# Sheet1.net
KiCad netlist of a schematic drawn in Altium Designer
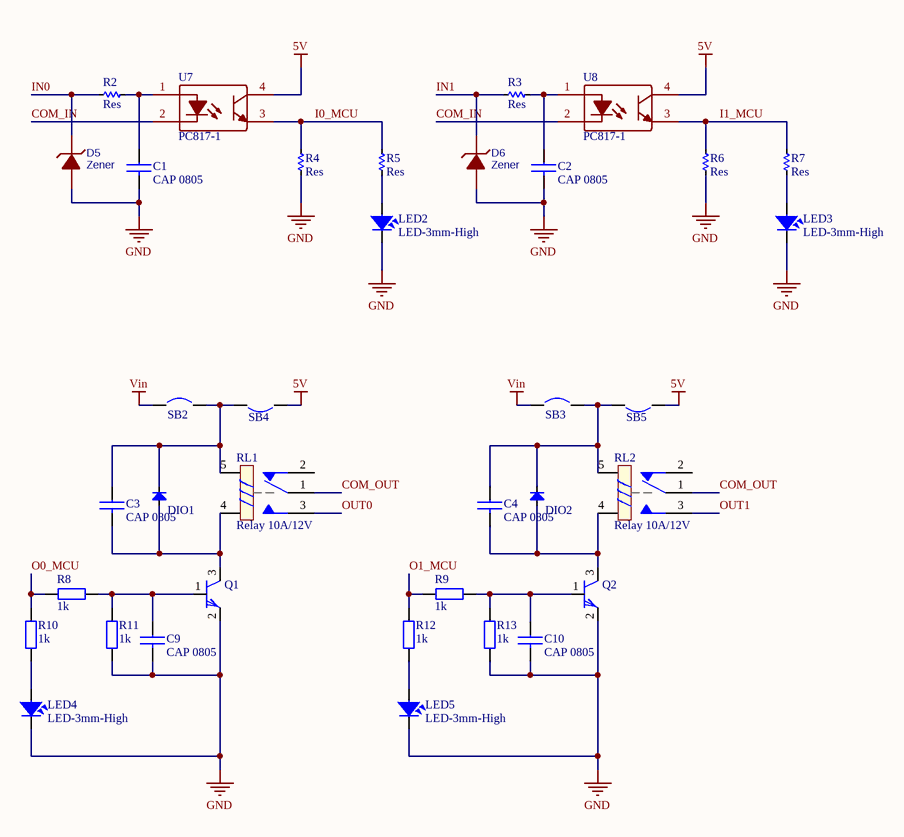
[diagram p0: Sheet1.SchDoc]

(export (version "E")
  (design (tool "Eeschema 10.0.6"))
  (components
    (comp (ref "C1") (value "CAP 0805") (footprint "0805") (libsource (lib "Cty1") (part "CAP 0805")))
    (comp (ref "C2") (value "CAP 0805") (footprint "0805") (libsource (lib "Cty1") (part "CAP 0805")))
    (comp (ref "C3") (value "CAP 0805") (footprint "0805") (libsource (lib "Cty1") (part "CAP 0805")))
    (comp (ref "C4") (value "CAP 0805") (footprint "0805") (libsource (lib "Cty1") (part "CAP 0805")))
    (comp (ref "C9") (value "CAP 0805") (footprint "0805") (libsource (lib "Cty1") (part "CAP 0805")))
    (comp (ref "C10") (value "CAP 0805") (footprint "0805") (libsource (lib "Cty1") (part "CAP 0805")))
    (comp (ref "D5")
      (value "Zener")
      (footprint "SOD80C")
      (fields
        (field (name "BOM_SUPPLIER PART") "C108433")
        (field (name "BOM_MANUFACTURER PART") "BZV55-C15")
        (field (name "CONTRIBUTOR") "LCSC")
      )
      (libsource (lib "Zener-Diode") (part "Zener"))
    )
    (comp (ref "D6")
      (value "Zener")
      (footprint "SOD80C")
      (fields
        (field (name "BOM_SUPPLIER PART") "C108433")
        (field (name "BOM_MANUFACTURER PART") "BZV55-C15")
        (field (name "CONTRIBUTOR") "LCSC")
      )
      (libsource (lib "Zener-Diode") (part "Zener"))
    )
    (comp (ref "DIO1")
      (value "Diode SMD")
      (footprint "DIO-SMD-106")
      (description "Default Diode")
      (fields (field (name "PUBLISHER") "Altium Limited"))
      (libsource (lib "Thư Viện Altium FULL HD") (part "Diode SMD"))
    )
    (comp (ref "DIO2")
      (value "Diode SMD")
      (footprint "DIO-SMD-106")
      (description "Default Diode")
      (fields (field (name "PUBLISHER") "Altium Limited"))
      (libsource (lib "Thư Viện Altium FULL HD") (part "Diode SMD"))
    )
    (comp (ref "LED2")
      (value "LED-3mm-High")
      (footprint "LED-3mm-High-Blue")
      (libsource (lib "LED-3mm-High") (part "LED-3mm-High"))
    )
    (comp (ref "LED3")
      (value "LED-3mm-High")
      (footprint "LED-3mm-High-Blue")
      (libsource (lib "LED-3mm-High") (part "LED-3mm-High"))
    )
    (comp (ref "LED4")
      (value "LED-3mm-High")
      (footprint "LED-3mm-High-Blue")
      (libsource (lib "LED-3mm-High") (part "LED-3mm-High"))
    )
    (comp (ref "LED5")
      (value "LED-3mm-High")
      (footprint "LED-3mm-High-Blue")
      (libsource (lib "LED-3mm-High") (part "LED-3mm-High"))
    )
    (comp (ref "Q1")
      (value "C1815")
      (footprint "SOT23 [C1815]")
      (description "Q2SC1815")
      (fields (field (name "PUBLISHER") "Hoang Nguyen"))
      (libsource (lib "hphonglib") (part "C1815"))
    )
    (comp (ref "Q2")
      (value "C1815")
      (footprint "SOT23 [C1815]")
      (description "Q2SC1815")
      (fields (field (name "PUBLISHER") "Hoang Nguyen"))
      (libsource (lib "hphonglib") (part "C1815"))
    )
    (comp (ref "R2")
      (value "Res")
      (footprint "RES-SMD-0805")
      (description "Resistor")
      (fields
        (field (name "MANUFACTURER") "Generic Components")
        (field (name "PUBLISHER") "Altium Hobart Technology Centre")
      )
      (libsource (lib "Thư Viện Altium FULL HD") (part "Res-SMD"))
    )
    (comp (ref "R3")
      (value "Res")
      (footprint "RES-SMD-0805")
      (description "Resistor")
      (fields
        (field (name "MANUFACTURER") "Generic Components")
        (field (name "PUBLISHER") "Altium Hobart Technology Centre")
      )
      (libsource (lib "Thư Viện Altium FULL HD") (part "Res-SMD"))
    )
    (comp (ref "R4")
      (value "Res")
      (footprint "RES-SMD-0805")
      (description "Resistor")
      (fields
        (field (name "MANUFACTURER") "Generic Components")
        (field (name "PUBLISHER") "Altium Hobart Technology Centre")
      )
      (libsource (lib "Thư Viện Altium FULL HD") (part "Res-SMD"))
    )
    (comp (ref "R5")
      (value "Res")
      (footprint "RES-SMD-0805")
      (description "Resistor")
      (fields
        (field (name "MANUFACTURER") "Generic Components")
        (field (name "PUBLISHER") "Altium Hobart Technology Centre")
      )
      (libsource (lib "Thư Viện Altium FULL HD") (part "Res-SMD"))
    )
    (comp (ref "R6")
      (value "Res")
      (footprint "RES-SMD-0805")
      (description "Resistor")
      (fields
        (field (name "MANUFACTURER") "Generic Components")
        (field (name "PUBLISHER") "Altium Hobart Technology Centre")
      )
      (libsource (lib "Thư Viện Altium FULL HD") (part "Res-SMD"))
    )
    (comp (ref "R7")
      (value "Res")
      (footprint "RES-SMD-0805")
      (description "Resistor")
      (fields
        (field (name "MANUFACTURER") "Generic Components")
        (field (name "PUBLISHER") "Altium Hobart Technology Centre")
      )
      (libsource (lib "Thư Viện Altium FULL HD") (part "Res-SMD"))
    )
    (comp (ref "R8")
      (value "1k")
      (footprint "SM-RES-0805")
      (description "Resistor 1/4W")
      (libsource (lib "syhaunguyen") (part "R1/4W"))
    )
    (comp (ref "R9")
      (value "1k")
      (footprint "SM-RES-0805")
      (description "Resistor 1/4W")
      (libsource (lib "syhaunguyen") (part "R1/4W"))
    )
    (comp (ref "R10")
      (value "1k")
      (footprint "SM-RES-0805")
      (description "Resistor 1/4W")
      (libsource (lib "syhaunguyen") (part "R1/4W"))
    )
    (comp (ref "R11")
      (value "1k")
      (footprint "SM-RES-0805")
      (description "Resistor 1/4W")
      (libsource (lib "syhaunguyen") (part "R1/4W"))
    )
    (comp (ref "R12")
      (value "1k")
      (footprint "SM-RES-0805")
      (description "Resistor 1/4W")
      (libsource (lib "syhaunguyen") (part "R1/4W"))
    )
    (comp (ref "R13")
      (value "1k")
      (footprint "SM-RES-0805")
      (description "Resistor 1/4W")
      (libsource (lib "syhaunguyen") (part "R1/4W"))
    )
    (comp (ref "RL1")
      (value "Relay 10A/12V")
      (footprint "RELAY 5")
      (description "Relay SPDT,10A - 12VDC 5 Pin")
      (libsource (lib "Thư Viện Altium FULL HD") (part "Relay 5"))
    )
    (comp (ref "RL2")
      (value "Relay 10A/12V")
      (footprint "RELAY 5")
      (description "Relay SPDT,10A - 12VDC 5 Pin")
      (libsource (lib "Thư Viện Altium FULL HD") (part "Relay 5"))
    )
    (comp (ref "SB2")
      (value "Circuit-Shorter")
      (footprint "Circuit-Shorter")
      (fields (field (name "PUBLISHER") "Altium Limited"))
      (libsource (lib "Circuit-Shorter") (part "Circuit-Shorter"))
    )
    (comp (ref "SB3")
      (value "Circuit-Shorter")
      (footprint "Circuit-Shorter")
      (fields (field (name "PUBLISHER") "Altium Limited"))
      (libsource (lib "Circuit-Shorter") (part "Circuit-Shorter"))
    )
    (comp (ref "SB4")
      (value "Circuit-Shorter")
      (footprint "Circuit-Shorter")
      (fields (field (name "PUBLISHER") "Altium Limited"))
      (libsource (lib "Circuit-Shorter") (part "Circuit-Shorter"))
    )
    (comp (ref "SB5")
      (value "Circuit-Shorter")
      (footprint "Circuit-Shorter")
      (fields (field (name "PUBLISHER") "Altium Limited"))
      (libsource (lib "Circuit-Shorter") (part "Circuit-Shorter"))
    )
    (comp (ref "U7") (value "PC817-1") (footprint "PC817-1-SMD") (libsource (lib "PC817") (part "PC817-1")))
    (comp (ref "U8") (value "PC817-1") (footprint "PC817-1-SMD") (libsource (lib "PC817") (part "PC817-1")))
  )
  (nets
    (net (code "1") (name "/COM_IN") (class "Default")
      (node (ref "U7") (pin "2") (pinfunction "CA_2") (pintype "passive"))
      (node (ref "U8") (pin "2") (pinfunction "CA_2") (pintype "passive"))
    )
    (net (code "2") (name "/COM_OUT") (class "Default")
      (node (ref "RL1") (pin "1") (pinfunction "1_1") (pintype "passive"))
      (node (ref "RL2") (pin "1") (pinfunction "1_1") (pintype "passive"))
    )
    (net (code "3") (name "/I0_MCU") (class "Default")
      (node (ref "R4") (pin "2") (pinfunction "2_2") (pintype "passive"))
      (node (ref "R5") (pin "1") (pinfunction "1_1") (pintype "passive"))
      (node (ref "U7") (pin "3") (pinfunction "EM_3") (pintype "passive"))
    )
    (net (code "4") (name "/I1_MCU") (class "Default")
      (node (ref "R6") (pin "2") (pinfunction "2_2") (pintype "passive"))
      (node (ref "R7") (pin "1") (pinfunction "1_1") (pintype "passive"))
      (node (ref "U8") (pin "3") (pinfunction "EM_3") (pintype "passive"))
    )
    (net (code "5") (name "/IN0") (class "Default")
      (node (ref "D5") (pin "2") (pinfunction "K_2") (pintype "passive"))
      (node (ref "R2") (pin "2") (pinfunction "2_2") (pintype "passive"))
    )
    (net (code "6") (name "/IN1") (class "Default")
      (node (ref "D6") (pin "2") (pinfunction "K_2") (pintype "passive"))
      (node (ref "R3") (pin "2") (pinfunction "2_2") (pintype "passive"))
    )
    (net (code "7") (name "/O0_MCU") (class "Default")
      (node (ref "R10") (pin "2") (pinfunction "2_2") (pintype "passive"))
      (node (ref "R8") (pin "2") (pinfunction "2_2") (pintype "passive"))
    )
    (net (code "8") (name "/O1_MCU") (class "Default")
      (node (ref "R12") (pin "2") (pinfunction "2_2") (pintype "passive"))
      (node (ref "R9") (pin "2") (pinfunction "2_2") (pintype "passive"))
    )
    (net (code "9") (name "/OUT0") (class "Default")
      (node (ref "RL1") (pin "3") (pinfunction "3_3") (pintype "passive"))
    )
    (net (code "10") (name "/OUT1") (class "Default")
      (node (ref "RL2") (pin "3") (pinfunction "3_3") (pintype "passive"))
    )
    (net (code "11") (name "5V") (class "Default")
      (node (ref "SB4") (pin "1") (pinfunction "1_1") (pintype "passive"))
      (node (ref "SB5") (pin "1") (pinfunction "1_1") (pintype "passive"))
      (node (ref "U7") (pin "4") (pinfunction "COL_4") (pintype "passive"))
      (node (ref "U8") (pin "4") (pinfunction "COL_4") (pintype "passive"))
    )
    (net (code "12") (name "GND") (class "Default")
      (node (ref "C1") (pin "2") (pinfunction "2_2") (pintype "passive"))
      (node (ref "C10") (pin "2") (pinfunction "2_2") (pintype "passive"))
      (node (ref "C2") (pin "2") (pinfunction "2_2") (pintype "passive"))
      (node (ref "C9") (pin "2") (pinfunction "2_2") (pintype "passive"))
      (node (ref "D5") (pin "1") (pinfunction "A_1") (pintype "passive"))
      (node (ref "D6") (pin "1") (pinfunction "A_1") (pintype "passive"))
      (node (ref "LED2") (pin "2") (pinfunction "K_2") (pintype "passive"))
      (node (ref "LED3") (pin "2") (pinfunction "K_2") (pintype "passive"))
      (node (ref "LED4") (pin "2") (pinfunction "K_2") (pintype "passive"))
      (node (ref "LED5") (pin "2") (pinfunction "K_2") (pintype "passive"))
      (node (ref "Q1") (pin "2") (pinfunction "E_2") (pintype "passive"))
      (node (ref "Q2") (pin "2") (pinfunction "E_2") (pintype "passive"))
      (node (ref "R11") (pin "2") (pinfunction "2_2") (pintype "passive"))
      (node (ref "R13") (pin "2") (pinfunction "2_2") (pintype "passive"))
      (node (ref "R4") (pin "1") (pinfunction "1_1") (pintype "passive"))
      (node (ref "R6") (pin "1") (pinfunction "1_1") (pintype "passive"))
    )
    (net (code "13") (name "Net-(DIO1-A)") (class "Default")
      (node (ref "C3") (pin "2") (pinfunction "2_2") (pintype "passive"))
      (node (ref "DIO1") (pin "1") (pinfunction "A_1") (pintype "passive"))
      (node (ref "Q1") (pin "3") (pinfunction "C_3") (pintype "passive"))
      (node (ref "RL1") (pin "4") (pinfunction "4_4") (pintype "passive"))
    )
    (net (code "14") (name "Net-(DIO1-K)") (class "Default")
      (node (ref "C3") (pin "1") (pinfunction "1_1") (pintype "passive"))
      (node (ref "DIO1") (pin "2") (pinfunction "K_2") (pintype "passive"))
      (node (ref "RL1") (pin "5") (pinfunction "5_5") (pintype "passive"))
      (node (ref "SB2") (pin "2") (pinfunction "2_2") (pintype "passive"))
      (node (ref "SB4") (pin "2") (pinfunction "2_2") (pintype "passive"))
    )
    (net (code "15") (name "Net-(DIO2-A)") (class "Default")
      (node (ref "C4") (pin "2") (pinfunction "2_2") (pintype "passive"))
      (node (ref "DIO2") (pin "1") (pinfunction "A_1") (pintype "passive"))
      (node (ref "Q2") (pin "3") (pinfunction "C_3") (pintype "passive"))
      (node (ref "RL2") (pin "4") (pinfunction "4_4") (pintype "passive"))
    )
    (net (code "16") (name "Net-(DIO2-K)") (class "Default")
      (node (ref "C4") (pin "1") (pinfunction "1_1") (pintype "passive"))
      (node (ref "DIO2") (pin "2") (pinfunction "K_2") (pintype "passive"))
      (node (ref "RL2") (pin "5") (pinfunction "5_5") (pintype "passive"))
      (node (ref "SB3") (pin "2") (pinfunction "2_2") (pintype "passive"))
      (node (ref "SB5") (pin "2") (pinfunction "2_2") (pintype "passive"))
    )
    (net (code "17") (name "Net-(LED2-A)") (class "Default")
      (node (ref "LED2") (pin "1") (pinfunction "A_1") (pintype "passive"))
      (node (ref "R5") (pin "2") (pinfunction "2_2") (pintype "passive"))
    )
    (net (code "18") (name "Net-(LED3-A)") (class "Default")
      (node (ref "LED3") (pin "1") (pinfunction "A_1") (pintype "passive"))
      (node (ref "R7") (pin "2") (pinfunction "2_2") (pintype "passive"))
    )
    (net (code "19") (name "Net-(LED4-A)") (class "Default")
      (node (ref "LED4") (pin "1") (pinfunction "A_1") (pintype "passive"))
      (node (ref "R10") (pin "1") (pinfunction "1_1") (pintype "passive"))
    )
    (net (code "20") (name "Net-(LED5-A)") (class "Default")
      (node (ref "LED5") (pin "1") (pinfunction "A_1") (pintype "passive"))
      (node (ref "R12") (pin "1") (pinfunction "1_1") (pintype "passive"))
    )
    (net (code "21") (name "Net-(Q1-B)") (class "Default")
      (node (ref "C9") (pin "1") (pinfunction "1_1") (pintype "passive"))
      (node (ref "Q1") (pin "1") (pinfunction "B_1") (pintype "passive"))
      (node (ref "R11") (pin "1") (pinfunction "1_1") (pintype "passive"))
      (node (ref "R8") (pin "1") (pinfunction "1_1") (pintype "passive"))
    )
    (net (code "22") (name "Net-(Q2-B)") (class "Default")
      (node (ref "C10") (pin "1") (pinfunction "1_1") (pintype "passive"))
      (node (ref "Q2") (pin "1") (pinfunction "B_1") (pintype "passive"))
      (node (ref "R13") (pin "1") (pinfunction "1_1") (pintype "passive"))
      (node (ref "R9") (pin "1") (pinfunction "1_1") (pintype "passive"))
    )
    (net (code "23") (name "Net-(U7-AN)") (class "Default")
      (node (ref "C1") (pin "1") (pinfunction "1_1") (pintype "passive"))
      (node (ref "R2") (pin "1") (pinfunction "1_1") (pintype "passive"))
      (node (ref "U7") (pin "1") (pinfunction "AN_1") (pintype "passive"))
    )
    (net (code "24") (name "Net-(U8-AN)") (class "Default")
      (node (ref "C2") (pin "1") (pinfunction "1_1") (pintype "passive"))
      (node (ref "R3") (pin "1") (pinfunction "1_1") (pintype "passive"))
      (node (ref "U8") (pin "1") (pinfunction "AN_1") (pintype "passive"))
    )
    (net (code "25") (name "Vin") (class "Default")
      (node (ref "SB2") (pin "1") (pinfunction "1_1") (pintype "passive"))
      (node (ref "SB3") (pin "1") (pinfunction "1_1") (pintype "passive"))
    )
    (net (code "26") (name "unconnected-(RL1-Pad2)") (class "Default")
      (node (ref "RL1") (pin "2") (pinfunction "2_2") (pintype "passive"))
    )
    (net (code "27") (name "unconnected-(RL2-Pad2)") (class "Default")
      (node (ref "RL2") (pin "2") (pinfunction "2_2") (pintype "passive"))
    )
  )
)
